# 1TTR4---_Cumbo_Fabio_---_PIC_Double.net
KiCad netlist of a schematic drawn in EAGLE
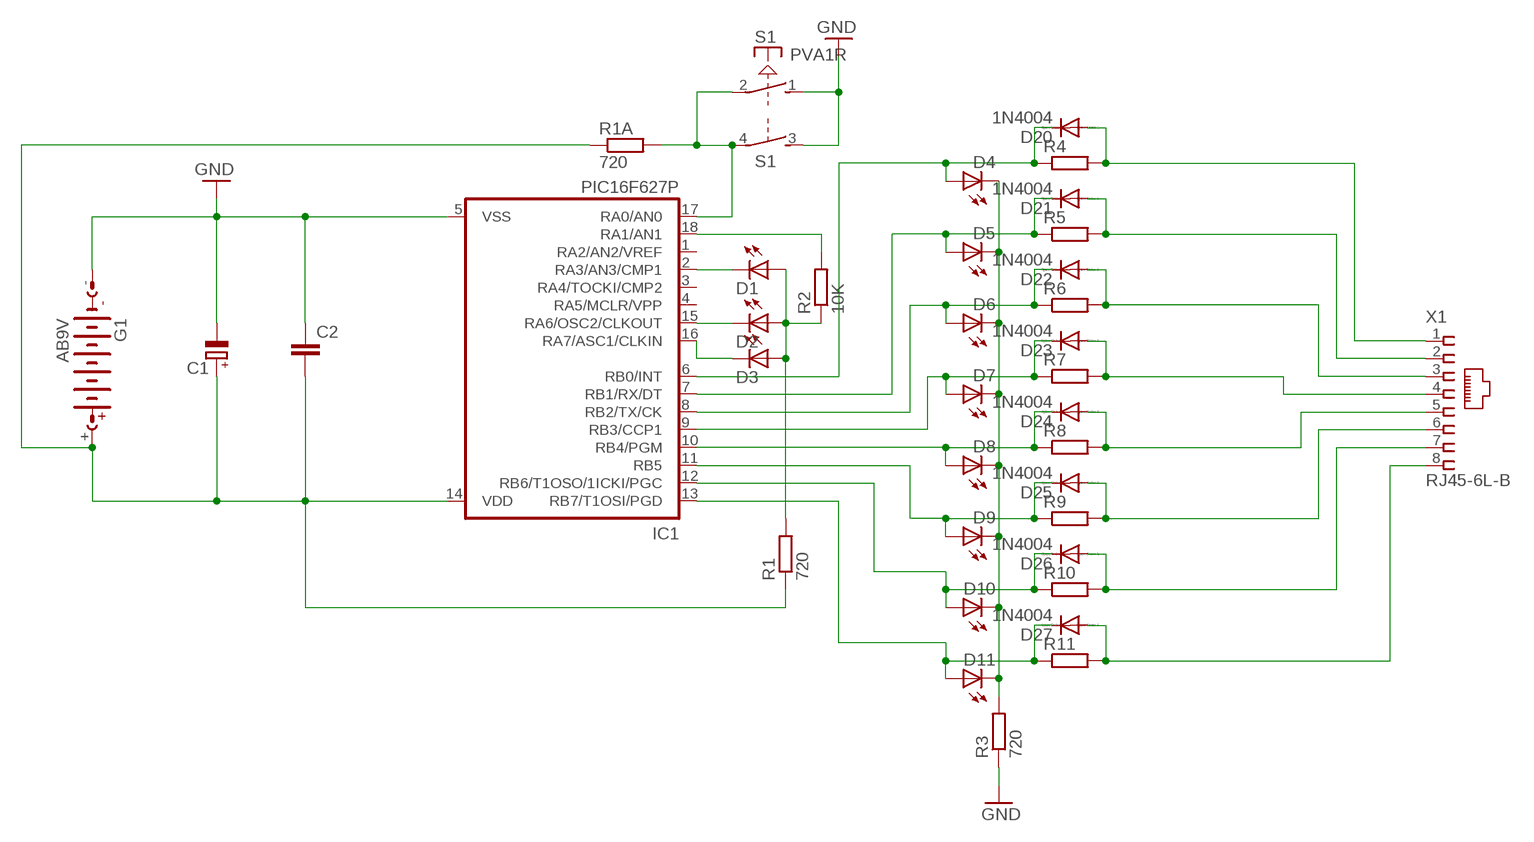
[diagram p0: schematic, sheet 1]

(export (version "E")
  (design (tool "Eeschema 10.0.6"))
  (components
    (comp (ref "C1")
      (value "CPOL-EUE5-6")
      (footprint "eagle-import:E5-6")
      (libsource (lib "eagle-import") (part "CPOL-EUE5-6"))
    )
    (comp (ref "C2")
      (value "C-EU050-024X044")
      (footprint "eagle-import:C050-024X044")
      (libsource (lib "eagle-import") (part "C-EU050-024X044"))
    )
    (comp (ref "D1")
      (value "LED5MM")
      (footprint "eagle-import:LED5MM")
      (libsource (lib "eagle-import") (part "LED5MM"))
    )
    (comp (ref "D2")
      (value "LED5MM")
      (footprint "eagle-import:LED5MM")
      (libsource (lib "eagle-import") (part "LED5MM"))
    )
    (comp (ref "D3")
      (value "LED5MM")
      (footprint "eagle-import:LED5MM")
      (libsource (lib "eagle-import") (part "LED5MM"))
    )
    (comp (ref "D4")
      (value "LED5MM")
      (footprint "eagle-import:LED5MM")
      (libsource (lib "eagle-import") (part "LED5MM"))
    )
    (comp (ref "D5")
      (value "LED5MM")
      (footprint "eagle-import:LED5MM")
      (libsource (lib "eagle-import") (part "LED5MM"))
    )
    (comp (ref "D6")
      (value "LED5MM")
      (footprint "eagle-import:LED5MM")
      (libsource (lib "eagle-import") (part "LED5MM"))
    )
    (comp (ref "D7")
      (value "LED5MM")
      (footprint "eagle-import:LED5MM")
      (libsource (lib "eagle-import") (part "LED5MM"))
    )
    (comp (ref "D8")
      (value "LED5MM")
      (footprint "eagle-import:LED5MM")
      (libsource (lib "eagle-import") (part "LED5MM"))
    )
    (comp (ref "D9")
      (value "LED5MM")
      (footprint "eagle-import:LED5MM")
      (libsource (lib "eagle-import") (part "LED5MM"))
    )
    (comp (ref "D10")
      (value "LED5MM")
      (footprint "eagle-import:LED5MM")
      (libsource (lib "eagle-import") (part "LED5MM"))
    )
    (comp (ref "D11")
      (value "LED5MM")
      (footprint "eagle-import:LED5MM")
      (libsource (lib "eagle-import") (part "LED5MM"))
    )
    (comp (ref "D20")
      (value "1N4004")
      (footprint "eagle-import:DO41-10")
      (libsource (lib "eagle-import") (part "1N4004"))
    )
    (comp (ref "D21")
      (value "1N4004")
      (footprint "eagle-import:DO41-10")
      (libsource (lib "eagle-import") (part "1N4004"))
    )
    (comp (ref "D22")
      (value "1N4004")
      (footprint "eagle-import:DO41-10")
      (libsource (lib "eagle-import") (part "1N4004"))
    )
    (comp (ref "D23")
      (value "1N4004")
      (footprint "eagle-import:DO41-10")
      (libsource (lib "eagle-import") (part "1N4004"))
    )
    (comp (ref "D24")
      (value "1N4004")
      (footprint "eagle-import:DO41-10")
      (libsource (lib "eagle-import") (part "1N4004"))
    )
    (comp (ref "D25")
      (value "1N4004")
      (footprint "eagle-import:DO41-10")
      (libsource (lib "eagle-import") (part "1N4004"))
    )
    (comp (ref "D26")
      (value "1N4004")
      (footprint "eagle-import:DO41-10")
      (libsource (lib "eagle-import") (part "1N4004"))
    )
    (comp (ref "D27")
      (value "1N4004")
      (footprint "eagle-import:DO41-10")
      (libsource (lib "eagle-import") (part "1N4004"))
    )
    (comp (ref "G1")
      (value "AB9V")
      (footprint "eagle-import:AB9V")
      (libsource (lib "eagle-import") (part "AB9V"))
    )
    (comp (ref "IC1")
      (value "PIC16F627P")
      (footprint "eagle-import:DIL18")
      (fields (field (name "MF") "MICROCHIP") (field (name "MPN") "PIC16F627-20I/P"))
      (libsource (lib "eagle-import") (part "PIC16F627P"))
    )
    (comp (ref "R1")
      (value "720")
      (footprint "eagle-import:0204_7")
      (libsource (lib "eagle-import") (part "R-EU_0204/7"))
    )
    (comp (ref "R1A")
      (value "720")
      (footprint "eagle-import:0204_7")
      (libsource (lib "eagle-import") (part "R-EU_0204/7"))
    )
    (comp (ref "R2")
      (value "10K")
      (footprint "eagle-import:0204_7")
      (libsource (lib "eagle-import") (part "R-EU_0204/7"))
    )
    (comp (ref "R3")
      (value "720")
      (footprint "eagle-import:0204_7")
      (libsource (lib "eagle-import") (part "R-EU_0204/7"))
    )
    (comp (ref "R4")
      (value "R-EU_0204/7")
      (footprint "eagle-import:0204_7")
      (libsource (lib "eagle-import") (part "R-EU_0204/7"))
    )
    (comp (ref "R5")
      (value "R-EU_0204/7")
      (footprint "eagle-import:0204_7")
      (libsource (lib "eagle-import") (part "R-EU_0204/7"))
    )
    (comp (ref "R6")
      (value "R-EU_0204/7")
      (footprint "eagle-import:0204_7")
      (libsource (lib "eagle-import") (part "R-EU_0204/7"))
    )
    (comp (ref "R7")
      (value "R-EU_0204/7")
      (footprint "eagle-import:0204_7")
      (libsource (lib "eagle-import") (part "R-EU_0204/7"))
    )
    (comp (ref "R8")
      (value "R-EU_0204/7")
      (footprint "eagle-import:0204_7")
      (libsource (lib "eagle-import") (part "R-EU_0204/7"))
    )
    (comp (ref "R9")
      (value "R-EU_0204/7")
      (footprint "eagle-import:0204_7")
      (libsource (lib "eagle-import") (part "R-EU_0204/7"))
    )
    (comp (ref "R10")
      (value "R-EU_0204/7")
      (footprint "eagle-import:0204_7")
      (libsource (lib "eagle-import") (part "R-EU_0204/7"))
    )
    (comp (ref "R11")
      (value "R-EU_0204/7")
      (footprint "eagle-import:0204_7")
      (libsource (lib "eagle-import") (part "R-EU_0204/7"))
    )
    (comp (ref "S1")
      (value "PVA1R")
      (footprint "eagle-import:PVA1R")
      (libsource (lib "eagle-import") (part "PVA1R"))
    )
    (comp (ref "X1")
      (value "RJ45-6L-B")
      (footprint "eagle-import:RJ45-NO-SHIELD")
      (libsource (lib "eagle-import") (part "RJ45-6L-B"))
    )
  )
  (nets
    (net (code "1") (name "GND") (class "Default")
      (node (ref "C1") (pin "-") (pinfunction "-_-") (pintype "passive"))
      (node (ref "C2") (pin "1") (pinfunction "1_1") (pintype "passive"))
      (node (ref "G1") (pin "-") (pinfunction "-_-") (pintype "passive"))
      (node (ref "IC1") (pin "5") (pinfunction "VSS_5") (pintype "power_in"))
      (node (ref "R3") (pin "1") (pinfunction "1_1") (pintype "passive"))
      (node (ref "S1") (pin "1") (pinfunction "S_1") (pintype "passive"))
      (node (ref "S1") (pin "3") (pinfunction "S_3") (pintype "passive"))
    )
    (net (code "2") (name "Net-(D1-C)") (class "Default")
      (node (ref "D1") (pin "K") (pinfunction "C_K") (pintype "passive"))
      (node (ref "IC1") (pin "2") (pinfunction "RA3/AN3/CMP1_2") (pintype "bidirectional"))
    )
    (net (code "3") (name "Net-(D1-PadA)") (class "Default")
      (node (ref "D1") (pin "A") (pinfunction "A_A") (pintype "passive"))
      (node (ref "D2") (pin "A") (pinfunction "A_A") (pintype "passive"))
      (node (ref "D3") (pin "A") (pinfunction "A_A") (pintype "passive"))
      (node (ref "R1") (pin "2") (pinfunction "2_2") (pintype "passive"))
      (node (ref "R2") (pin "1") (pinfunction "1_1") (pintype "passive"))
    )
    (net (code "4") (name "Net-(D2-C)") (class "Default")
      (node (ref "D2") (pin "K") (pinfunction "C_K") (pintype "passive"))
      (node (ref "IC1") (pin "15") (pinfunction "RA6/OSC2/CLKOUT_15") (pintype "bidirectional"))
    )
    (net (code "5") (name "Net-(D3-C)") (class "Default")
      (node (ref "D3") (pin "K") (pinfunction "C_K") (pintype "passive"))
      (node (ref "IC1") (pin "16") (pinfunction "RA7/ASC1/CLKIN_16") (pintype "bidirectional"))
    )
    (net (code "6") (name "Net-(D10-C)") (class "Default")
      (node (ref "D10") (pin "K") (pinfunction "C_K") (pintype "passive"))
      (node (ref "D11") (pin "K") (pinfunction "C_K") (pintype "passive"))
      (node (ref "D4") (pin "K") (pinfunction "C_K") (pintype "passive"))
      (node (ref "D5") (pin "K") (pinfunction "C_K") (pintype "passive"))
      (node (ref "D6") (pin "K") (pinfunction "C_K") (pintype "passive"))
      (node (ref "D7") (pin "K") (pinfunction "C_K") (pintype "passive"))
      (node (ref "D8") (pin "K") (pinfunction "C_K") (pintype "passive"))
      (node (ref "D9") (pin "K") (pinfunction "C_K") (pintype "passive"))
      (node (ref "R3") (pin "2") (pinfunction "2_2") (pintype "passive"))
    )
    (net (code "7") (name "Net-(D20-PadA)") (class "Default")
      (node (ref "D20") (pin "A") (pinfunction "A_A") (pintype "passive"))
      (node (ref "R4") (pin "2") (pinfunction "2_2") (pintype "passive"))
      (node (ref "X1") (pin "1") (pinfunction "1_1") (pintype "passive"))
    )
    (net (code "8") (name "Net-(D21-PadA)") (class "Default")
      (node (ref "D21") (pin "A") (pinfunction "A_A") (pintype "passive"))
      (node (ref "R5") (pin "2") (pinfunction "2_2") (pintype "passive"))
      (node (ref "X1") (pin "2") (pinfunction "2_2") (pintype "passive"))
    )
    (net (code "9") (name "Net-(D22-PadA)") (class "Default")
      (node (ref "D22") (pin "A") (pinfunction "A_A") (pintype "passive"))
      (node (ref "R6") (pin "2") (pinfunction "2_2") (pintype "passive"))
      (node (ref "X1") (pin "3") (pinfunction "3_3") (pintype "passive"))
    )
    (net (code "10") (name "Net-(D23-PadA)") (class "Default")
      (node (ref "D23") (pin "A") (pinfunction "A_A") (pintype "passive"))
      (node (ref "R7") (pin "2") (pinfunction "2_2") (pintype "passive"))
      (node (ref "X1") (pin "4") (pinfunction "4_4") (pintype "passive"))
    )
    (net (code "11") (name "Net-(D24-PadA)") (class "Default")
      (node (ref "D24") (pin "A") (pinfunction "A_A") (pintype "passive"))
      (node (ref "R8") (pin "2") (pinfunction "2_2") (pintype "passive"))
      (node (ref "X1") (pin "5") (pinfunction "5_5") (pintype "passive"))
    )
    (net (code "12") (name "Net-(D25-PadA)") (class "Default")
      (node (ref "D25") (pin "A") (pinfunction "A_A") (pintype "passive"))
      (node (ref "R9") (pin "2") (pinfunction "2_2") (pintype "passive"))
      (node (ref "X1") (pin "6") (pinfunction "6_6") (pintype "passive"))
    )
    (net (code "13") (name "Net-(D26-PadA)") (class "Default")
      (node (ref "D26") (pin "A") (pinfunction "A_A") (pintype "passive"))
      (node (ref "R10") (pin "2") (pinfunction "2_2") (pintype "passive"))
      (node (ref "X1") (pin "7") (pinfunction "7_7") (pintype "passive"))
    )
    (net (code "14") (name "Net-(D27-PadA)") (class "Default")
      (node (ref "D27") (pin "A") (pinfunction "A_A") (pintype "passive"))
      (node (ref "R11") (pin "2") (pinfunction "2_2") (pintype "passive"))
      (node (ref "X1") (pin "8") (pinfunction "8_8") (pintype "passive"))
    )
    (net (code "15") (name "Net-(IC1-RA0{slash}AN0)") (class "Default")
      (node (ref "IC1") (pin "17") (pinfunction "RA0/AN0_17") (pintype "bidirectional"))
      (node (ref "R1A") (pin "2") (pinfunction "2_2") (pintype "passive"))
      (node (ref "S1") (pin "2") (pinfunction "P_2") (pintype "passive"))
      (node (ref "S1") (pin "4") (pinfunction "P_4") (pintype "passive"))
    )
    (net (code "16") (name "Net-(IC1-RA1{slash}AN1)") (class "Default")
      (node (ref "IC1") (pin "18") (pinfunction "RA1/AN1_18") (pintype "bidirectional"))
      (node (ref "R2") (pin "2") (pinfunction "2_2") (pintype "passive"))
    )
    (net (code "17") (name "Net-(IC1-RB0{slash}INT)") (class "Default")
      (node (ref "D20") (pin "C") (pinfunction "C_C") (pintype "passive"))
      (node (ref "D4") (pin "A") (pinfunction "A_A") (pintype "passive"))
      (node (ref "IC1") (pin "6") (pinfunction "RB0/INT_6") (pintype "bidirectional"))
      (node (ref "R4") (pin "1") (pinfunction "1_1") (pintype "passive"))
    )
    (net (code "18") (name "Net-(IC1-RB1{slash}RX{slash}DT)") (class "Default")
      (node (ref "D21") (pin "C") (pinfunction "C_C") (pintype "passive"))
      (node (ref "D5") (pin "A") (pinfunction "A_A") (pintype "passive"))
      (node (ref "IC1") (pin "7") (pinfunction "RB1/RX/DT_7") (pintype "bidirectional"))
      (node (ref "R5") (pin "1") (pinfunction "1_1") (pintype "passive"))
    )
    (net (code "19") (name "Net-(IC1-RB2{slash}TX{slash}CK)") (class "Default")
      (node (ref "D22") (pin "C") (pinfunction "C_C") (pintype "passive"))
      (node (ref "D6") (pin "A") (pinfunction "A_A") (pintype "passive"))
      (node (ref "IC1") (pin "8") (pinfunction "RB2/TX/CK_8") (pintype "bidirectional"))
      (node (ref "R6") (pin "1") (pinfunction "1_1") (pintype "passive"))
    )
    (net (code "20") (name "Net-(IC1-RB3{slash}CCP1)") (class "Default")
      (node (ref "D23") (pin "C") (pinfunction "C_C") (pintype "passive"))
      (node (ref "D7") (pin "A") (pinfunction "A_A") (pintype "passive"))
      (node (ref "IC1") (pin "9") (pinfunction "RB3/CCP1_9") (pintype "bidirectional"))
      (node (ref "R7") (pin "1") (pinfunction "1_1") (pintype "passive"))
    )
    (net (code "21") (name "Net-(IC1-RB4{slash}PGM)") (class "Default")
      (node (ref "D24") (pin "C") (pinfunction "C_C") (pintype "passive"))
      (node (ref "D8") (pin "A") (pinfunction "A_A") (pintype "passive"))
      (node (ref "IC1") (pin "10") (pinfunction "RB4/PGM_10") (pintype "bidirectional"))
      (node (ref "R8") (pin "1") (pinfunction "1_1") (pintype "passive"))
    )
    (net (code "22") (name "Net-(IC1-RB5)") (class "Default")
      (node (ref "D25") (pin "C") (pinfunction "C_C") (pintype "passive"))
      (node (ref "D9") (pin "A") (pinfunction "A_A") (pintype "passive"))
      (node (ref "IC1") (pin "11") (pinfunction "RB5_11") (pintype "bidirectional"))
      (node (ref "R9") (pin "1") (pinfunction "1_1") (pintype "passive"))
    )
    (net (code "23") (name "Net-(IC1-RB6{slash}T1OSO{slash}1ICKI{slash}PGC)") (class "Default")
      (node (ref "D10") (pin "A") (pinfunction "A_A") (pintype "passive"))
      (node (ref "D26") (pin "C") (pinfunction "C_C") (pintype "passive"))
      (node (ref "IC1") (pin "12") (pinfunction "RB6/T1OSO/1ICKI/PGC_12") (pintype "bidirectional"))
      (node (ref "R10") (pin "1") (pinfunction "1_1") (pintype "passive"))
    )
    (net (code "24") (name "Net-(IC1-RB7{slash}T1OSI{slash}PGD)") (class "Default")
      (node (ref "D11") (pin "A") (pinfunction "A_A") (pintype "passive"))
      (node (ref "D27") (pin "C") (pinfunction "C_C") (pintype "passive"))
      (node (ref "IC1") (pin "13") (pinfunction "RB7/T1OSI/PGD_13") (pintype "bidirectional"))
      (node (ref "R11") (pin "1") (pinfunction "1_1") (pintype "passive"))
    )
    (net (code "25") (name "Net-(IC1-VDD)") (class "Default")
      (node (ref "C1") (pin "+") (pinfunction "+_+") (pintype "passive"))
      (node (ref "C2") (pin "2") (pinfunction "2_2") (pintype "passive"))
      (node (ref "G1") (pin "+") (pinfunction "+_+") (pintype "passive"))
      (node (ref "IC1") (pin "14") (pinfunction "VDD_14") (pintype "power_in"))
      (node (ref "R1") (pin "1") (pinfunction "1_1") (pintype "passive"))
      (node (ref "R1A") (pin "1") (pinfunction "1_1") (pintype "passive"))
    )
    (net (code "26") (name "unconnected-(IC1-RA2{slash}AN2{slash}VREF-Pad1)") (class "Default")
      (node (ref "IC1") (pin "1") (pinfunction "RA2/AN2/VREF_1") (pintype "bidirectional"))
    )
    (net (code "27") (name "unconnected-(IC1-RA4{slash}TOCKI{slash}CMP2-Pad3)") (class "Default")
      (node (ref "IC1") (pin "3") (pinfunction "RA4/TOCKI/CMP2_3") (pintype "bidirectional"))
    )
    (net (code "28") (name "unconnected-(IC1-RA5{slash}MCLR{slash}VPP-Pad4)") (class "Default")
      (node (ref "IC1") (pin "4") (pinfunction "RA5/MCLR/VPP_4") (pintype "input"))
    )
  )
)
